# WixelTherm.net
KiCad netlist of a schematic drawn in EAGLE
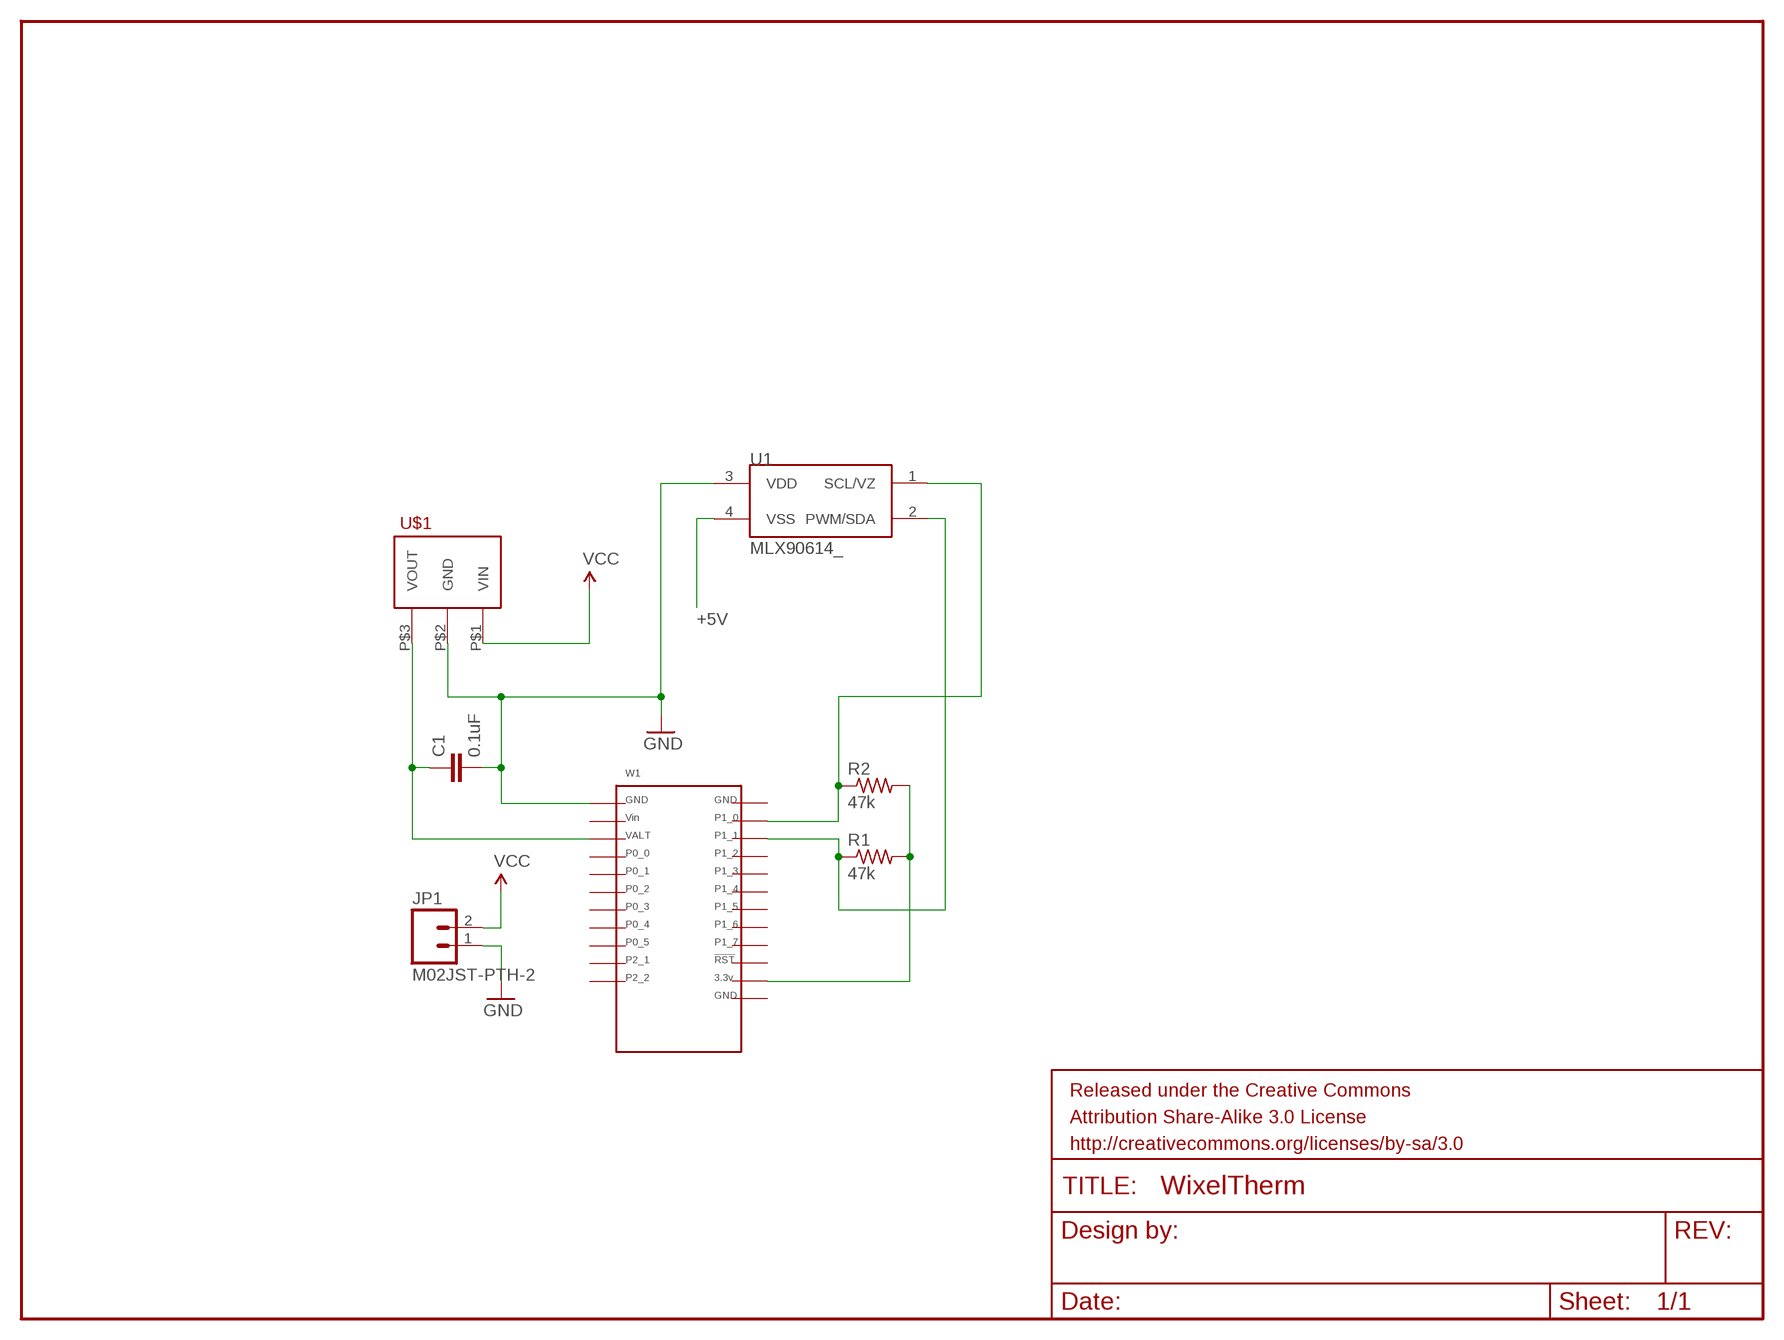
[diagram p0: schematic, sheet 1]

(export (version "E")
  (design (tool "Eeschema 10.0.6"))
  (components
    (comp (ref "C1")
      (value "0.1uF")
      (footprint "eagle-import:0603-CAP")
      (libsource (lib "eagle-import") (part "0.1UF-25V(+80/-20%)(0603)"))
    )
    (comp (ref "FRAME1")
      (value "FRAME-LETTER")
      (footprint "eagle-import:CREATIVE_COMMONS")
      (libsource (lib "eagle-import") (part "FRAME-LETTER"))
    )
    (comp (ref "JP1")
      (value "M02JST-PTH-2")
      (footprint "eagle-import:JST-2-PTH")
      (libsource (lib "eagle-import") (part "M02JST-PTH-2"))
    )
    (comp (ref "R1")
      (value "47k")
      (footprint "eagle-import:0207_10")
      (libsource (lib "eagle-import") (part "R-US_0207/10"))
    )
    (comp (ref "R2")
      (value "47k")
      (footprint "eagle-import:0207_10")
      (libsource (lib "eagle-import") (part "R-US_0207/10"))
    )
    (comp (ref "U$1")
      (value "POLOLU_NCP1402")
      (footprint "eagle-import:POLOLU_BREAKOUT")
      (libsource (lib "eagle-import") (part "POLOLU_NCP1402"))
    )
    (comp (ref "U1")
      (value "MLX90614_")
      (footprint "eagle-import:TO-39")
      (libsource (lib "eagle-import") (part "MLX90614_"))
    )
    (comp (ref "W1")
      (value "WIXEL")
      (footprint "eagle-import:WIXEL")
      (libsource (lib "eagle-import") (part "WIXEL"))
    )
  )
  (nets
    (net (code "1") (name "/+5V") (class "Default")
      (node (ref "C1") (pin "1") (pinfunction "1_1") (pintype "passive"))
      (node (ref "U$1") (pin "P$3") (pinfunction "VOUT_P$3") (pintype "bidirectional"))
      (node (ref "U1") (pin "4") (pinfunction "VSS_4") (pintype "bidirectional"))
      (node (ref "W1") (pin "P$3") (pinfunction "P$3_P$3") (pintype "bidirectional"))
    )
    (net (code "2") (name "GND") (class "Default")
      (node (ref "C1") (pin "2") (pinfunction "2_2") (pintype "passive"))
      (node (ref "JP1") (pin "1") (pinfunction "1_1") (pintype "passive"))
      (node (ref "U$1") (pin "P$2") (pinfunction "GND_P$2") (pintype "bidirectional"))
      (node (ref "U1") (pin "3") (pinfunction "VDD_3") (pintype "bidirectional"))
      (node (ref "W1") (pin "P$1") (pinfunction "P$1_P$1") (pintype "bidirectional"))
    )
    (net (code "3") (name "Net-(R1-Pad2)") (class "Default")
      (node (ref "R1") (pin "2") (pinfunction "2_2") (pintype "passive"))
      (node (ref "R2") (pin "2") (pinfunction "2_2") (pintype "passive"))
      (node (ref "W1") (pin "P$22") (pinfunction "P$22_P$22") (pintype "bidirectional"))
    )
    (net (code "4") (name "Net-(U1-PWM{slash}SDA)") (class "Default")
      (node (ref "R1") (pin "1") (pinfunction "1_1") (pintype "passive"))
      (node (ref "U1") (pin "2") (pinfunction "PWM/SDA_2") (pintype "bidirectional"))
      (node (ref "W1") (pin "P$14") (pinfunction "P$14_P$14") (pintype "bidirectional"))
    )
    (net (code "5") (name "Net-(U1-SCL{slash}VZ)") (class "Default")
      (node (ref "R2") (pin "1") (pinfunction "1_1") (pintype "passive"))
      (node (ref "U1") (pin "1") (pinfunction "SCL/VZ_1") (pintype "bidirectional"))
      (node (ref "W1") (pin "P$13") (pinfunction "P$13_P$13") (pintype "bidirectional"))
    )
    (net (code "6") (name "VCC") (class "Default")
      (node (ref "JP1") (pin "2") (pinfunction "2_2") (pintype "passive"))
      (node (ref "U$1") (pin "P$1") (pinfunction "VIN_P$1") (pintype "bidirectional"))
    )
    (net (code "7") (name "unconnected-(W1-PadP$2)") (class "Default")
      (node (ref "W1") (pin "P$2") (pinfunction "P$2_P$2") (pintype "bidirectional"))
    )
    (net (code "8") (name "unconnected-(W1-PadP$4)") (class "Default")
      (node (ref "W1") (pin "P$4") (pinfunction "P$4_P$4") (pintype "bidirectional"))
    )
    (net (code "9") (name "unconnected-(W1-PadP$5)") (class "Default")
      (node (ref "W1") (pin "P$5") (pinfunction "P$5_P$5") (pintype "bidirectional"))
    )
    (net (code "10") (name "unconnected-(W1-PadP$6)") (class "Default")
      (node (ref "W1") (pin "P$6") (pinfunction "P$6_P$6") (pintype "bidirectional"))
    )
    (net (code "11") (name "unconnected-(W1-PadP$7)") (class "Default")
      (node (ref "W1") (pin "P$7") (pinfunction "P$7_P$7") (pintype "bidirectional"))
    )
    (net (code "12") (name "unconnected-(W1-PadP$8)") (class "Default")
      (node (ref "W1") (pin "P$8") (pinfunction "P$8_P$8") (pintype "bidirectional"))
    )
    (net (code "13") (name "unconnected-(W1-PadP$9)") (class "Default")
      (node (ref "W1") (pin "P$9") (pinfunction "P$9_P$9") (pintype "bidirectional"))
    )
    (net (code "14") (name "unconnected-(W1-PadP$10)") (class "Default")
      (node (ref "W1") (pin "P$10") (pinfunction "P$10_P$10") (pintype "bidirectional"))
    )
    (net (code "15") (name "unconnected-(W1-PadP$11)") (class "Default")
      (node (ref "W1") (pin "P$11") (pinfunction "P$11_P$11") (pintype "bidirectional"))
    )
    (net (code "16") (name "unconnected-(W1-PadP$12)") (class "Default")
      (node (ref "W1") (pin "P$12") (pinfunction "P$12_P$12") (pintype "bidirectional"))
    )
    (net (code "17") (name "unconnected-(W1-PadP$15)") (class "Default")
      (node (ref "W1") (pin "P$15") (pinfunction "P$15_P$15") (pintype "bidirectional"))
    )
    (net (code "18") (name "unconnected-(W1-PadP$16)") (class "Default")
      (node (ref "W1") (pin "P$16") (pinfunction "P$16_P$16") (pintype "bidirectional"))
    )
    (net (code "19") (name "unconnected-(W1-PadP$17)") (class "Default")
      (node (ref "W1") (pin "P$17") (pinfunction "P$17_P$17") (pintype "bidirectional"))
    )
    (net (code "20") (name "unconnected-(W1-PadP$18)") (class "Default")
      (node (ref "W1") (pin "P$18") (pinfunction "P$18_P$18") (pintype "bidirectional"))
    )
    (net (code "21") (name "unconnected-(W1-PadP$19)") (class "Default")
      (node (ref "W1") (pin "P$19") (pinfunction "P$19_P$19") (pintype "bidirectional"))
    )
    (net (code "22") (name "unconnected-(W1-PadP$20)") (class "Default")
      (node (ref "W1") (pin "P$20") (pinfunction "P$20_P$20") (pintype "bidirectional"))
    )
    (net (code "23") (name "unconnected-(W1-PadP$21)") (class "Default")
      (node (ref "W1") (pin "P$21") (pinfunction "P$21_P$21") (pintype "bidirectional"))
    )
    (net (code "24") (name "unconnected-(W1-PadP$23)") (class "Default")
      (node (ref "W1") (pin "P$23") (pinfunction "P$23_P$23") (pintype "bidirectional"))
    )
  )
)
